# sliding_protentiometer-v1_0.net
KiCad netlist of a schematic drawn in EAGLE
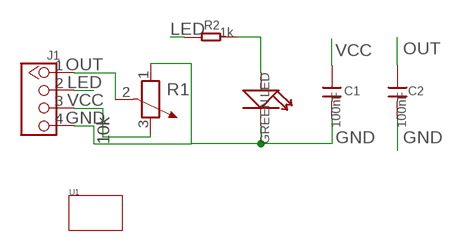
[diagram p0: schematic, sheet 1]

(export (version "E")
  (design (tool "Eeschema 10.0.6"))
  (components
    (comp (ref "C1")
      (value "100nF")
      (footprint "eagle-import:0805")
      (libsource (lib "eagle-import") (part "C-0805"))
    )
    (comp (ref "C2")
      (value "100nF")
      (footprint "eagle-import:0805")
      (libsource (lib "eagle-import") (part "C-0805"))
    )
    (comp (ref "J1")
      (value "TWIG-4P-2.0-2.0")
      (footprint "eagle-import:4P-2.0")
      (libsource (lib "eagle-import") (part "TWIG-4P-2.0-2.0"))
    )
    (comp (ref "LED")
      (value "GREEN")
      (footprint "eagle-import:LED-0805")
      (libsource (lib "eagle-import") (part "LED'0805'"))
    )
    (comp (ref "R1")
      (value "10k")
      (footprint "eagle-import:3P-SQUA-45.6X10X5.8H")
      (libsource (lib "eagle-import") (part "R-POTENTIOMETER"))
    )
    (comp (ref "R2")
      (value "1k")
      (footprint "eagle-import:0805")
      (libsource (lib "eagle-import") (part "R-0805"))
    )
    (comp (ref "U1")
      (value "TWIG'3U'")
      (footprint "eagle-import:3U-DIM-W_-DRILL")
      (libsource (lib "eagle-import") (part "TWIG'3U'"))
    )
  )
  (nets
    (net (code "1") (name "/GND") (class "Default")
      (node (ref "C1") (pin "2") (pinfunction "2_2") (pintype "passive"))
      (node (ref "C2") (pin "2") (pinfunction "2_2") (pintype "passive"))
      (node (ref "J1") (pin "4") (pinfunction "4_4") (pintype "bidirectional"))
      (node (ref "LED") (pin "-") (pinfunction "-_-") (pintype "passive"))
      (node (ref "R1") (pin "1") (pinfunction "1_1") (pintype "passive"))
    )
    (net (code "2") (name "/LED") (class "Default")
      (node (ref "J1") (pin "2") (pinfunction "2_2") (pintype "bidirectional"))
      (node (ref "R2") (pin "1") (pinfunction "1_1") (pintype "passive"))
    )
    (net (code "3") (name "/OUT") (class "Default")
      (node (ref "C2") (pin "1") (pinfunction "1_1") (pintype "passive"))
      (node (ref "J1") (pin "1") (pinfunction "1_1") (pintype "bidirectional"))
      (node (ref "R1") (pin "2") (pinfunction "3_2") (pintype "passive"))
    )
    (net (code "4") (name "/VCC") (class "Default")
      (node (ref "C1") (pin "1") (pinfunction "1_1") (pintype "passive"))
      (node (ref "J1") (pin "3") (pinfunction "3_3") (pintype "bidirectional"))
      (node (ref "R1") (pin "3") (pinfunction "2_3") (pintype "passive"))
    )
    (net (code "5") (name "Net-(LED-Pad+)") (class "Default")
      (node (ref "LED") (pin "+") (pinfunction "+_+") (pintype "passive"))
      (node (ref "R2") (pin "2") (pinfunction "2_2") (pintype "passive"))
    )
  )
)
